# Smarty-BOTTOM.net
KiCad netlist of a schematic drawn in EAGLE
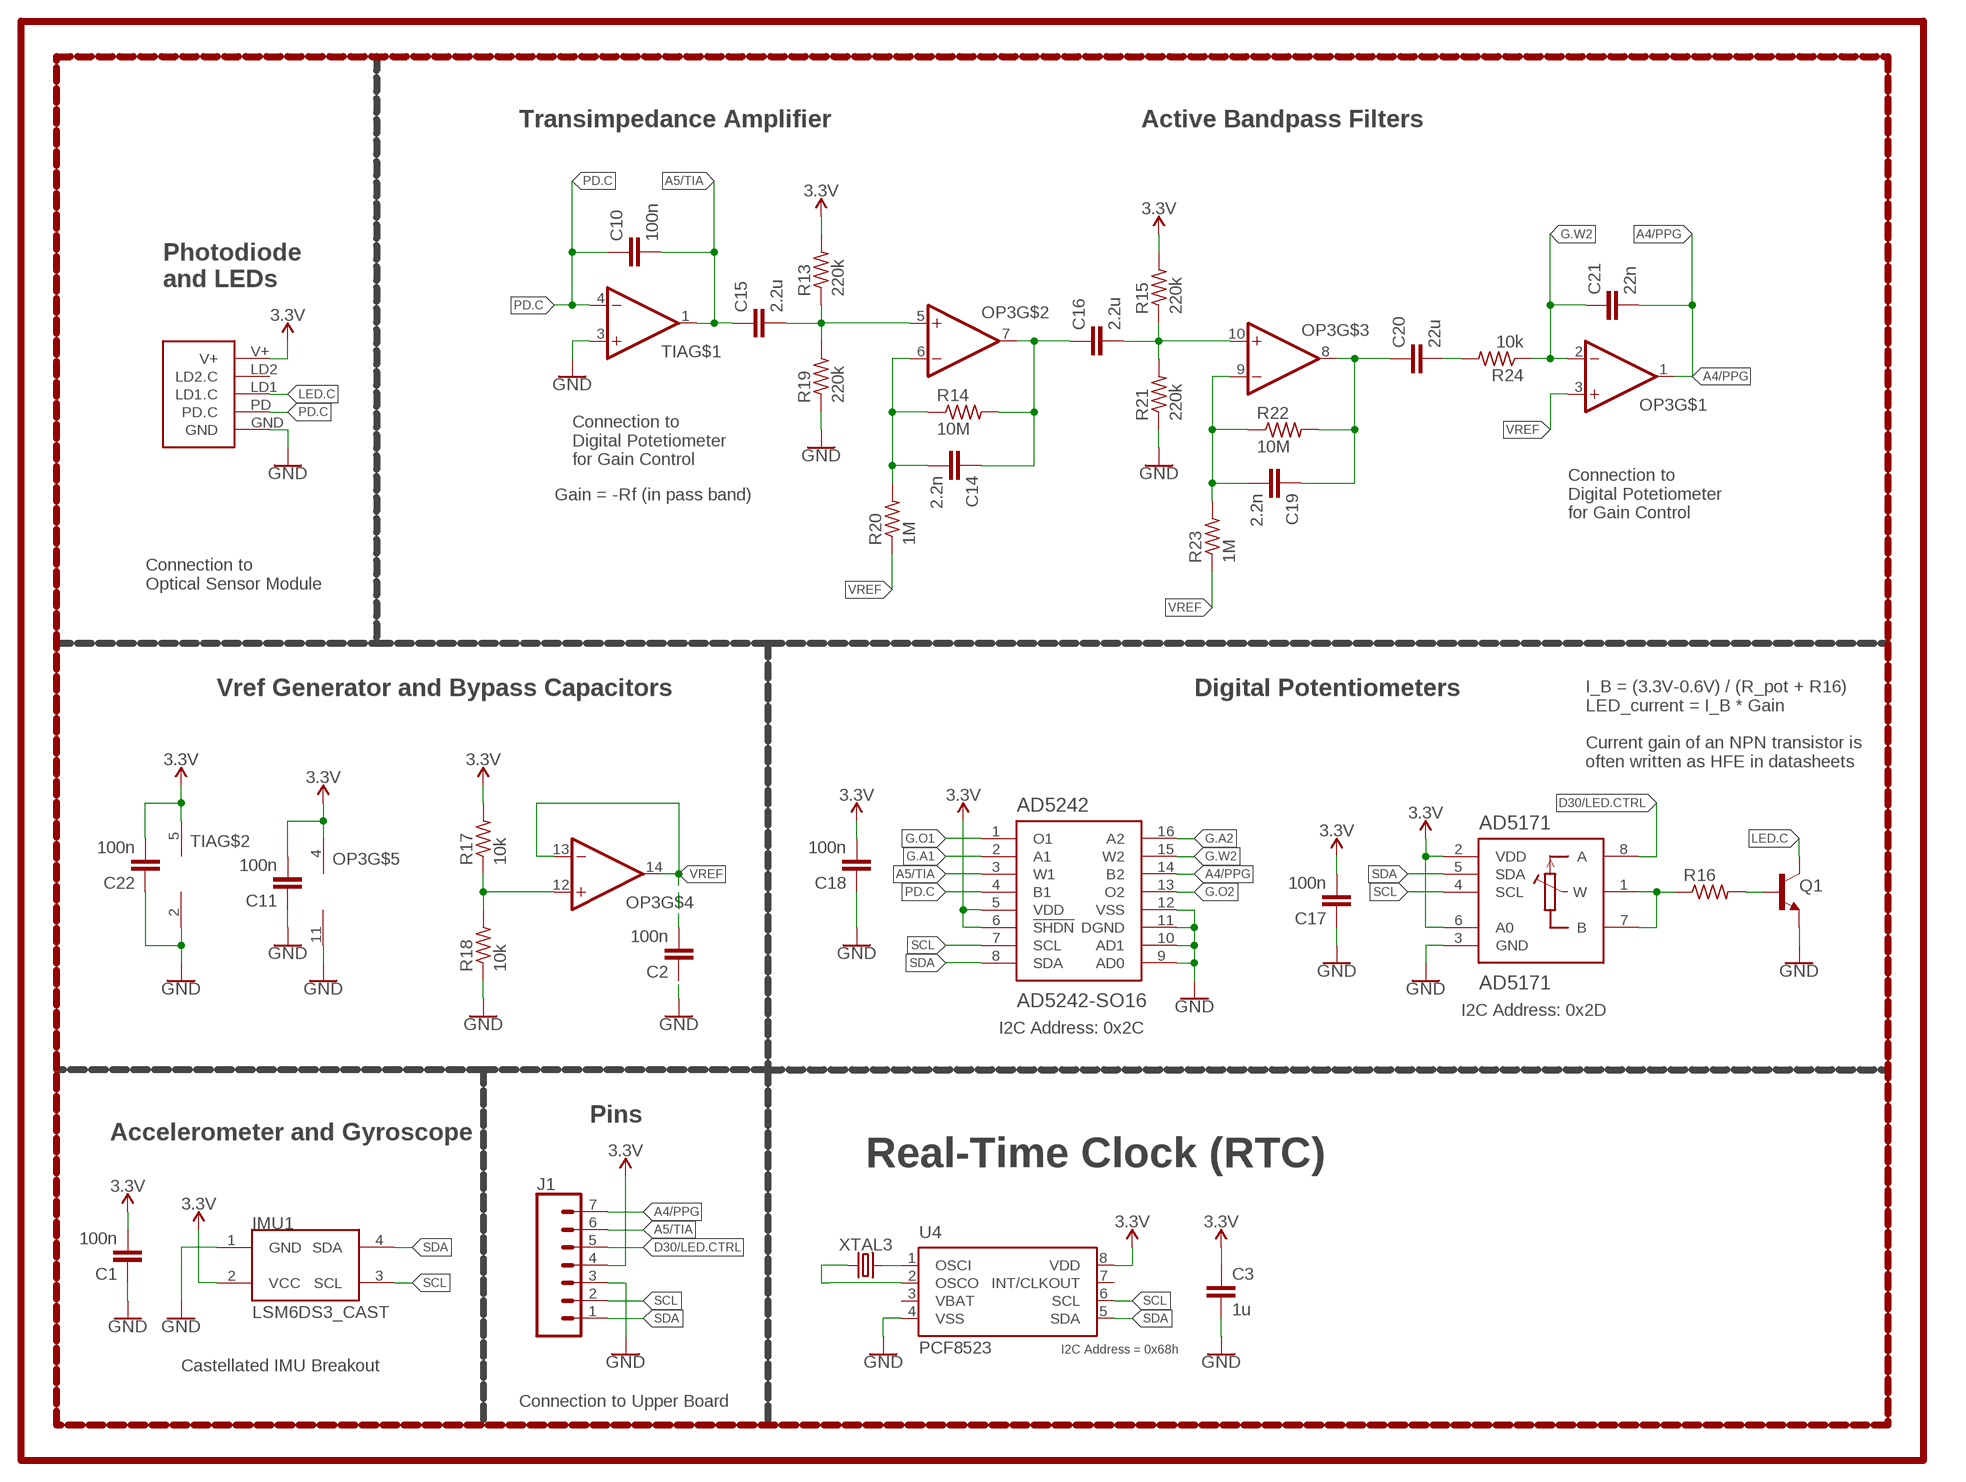
[diagram p0: schematic, sheet 1]

(export (version "E")
  (design (tool "Eeschema 10.0.6"))
  (components
    (comp (ref "AD5171")
      (value "AD5171")
      (footprint "eagle-import:SOT-23-8")
      (libsource (lib "eagle-import") (part "AD5171"))
    )
    (comp (ref "AD5242")
      (value "AD5242-SO16")
      (footprint "eagle-import:SO16")
      (libsource (lib "eagle-import") (part "AD5242-SO16"))
    )
    (comp (ref "C1")
      (value "100n")
      (footprint "eagle-import:C0603")
      (libsource (lib "eagle-import") (part "CAPACITOR0603"))
    )
    (comp (ref "C2")
      (value "100n")
      (footprint "eagle-import:C0603")
      (libsource (lib "eagle-import") (part "CAPACITOR0603"))
    )
    (comp (ref "C3")
      (value "1u")
      (footprint "eagle-import:C0603")
      (libsource (lib "eagle-import") (part "CAPACITOR0603"))
    )
    (comp (ref "C10")
      (value "100n")
      (footprint "eagle-import:C0603")
      (libsource (lib "eagle-import") (part "CAPACITOR0603"))
    )
    (comp (ref "C11")
      (value "100n")
      (footprint "eagle-import:C0603")
      (libsource (lib "eagle-import") (part "CAPACITOR0603"))
    )
    (comp (ref "C14")
      (value "2.2n")
      (footprint "eagle-import:C0603")
      (libsource (lib "eagle-import") (part "CAPACITOR0603"))
    )
    (comp (ref "C15")
      (value "2.2u")
      (footprint "eagle-import:C0603")
      (libsource (lib "eagle-import") (part "CAPACITOR0603"))
    )
    (comp (ref "C16")
      (value "2.2u")
      (footprint "eagle-import:C0603")
      (libsource (lib "eagle-import") (part "CAPACITOR0603"))
    )
    (comp (ref "C17")
      (value "100n")
      (footprint "eagle-import:C0603")
      (libsource (lib "eagle-import") (part "CAPACITOR0603"))
    )
    (comp (ref "C18")
      (value "100n")
      (footprint "eagle-import:C0603")
      (libsource (lib "eagle-import") (part "CAPACITOR0603"))
    )
    (comp (ref "C19")
      (value "2.2n")
      (footprint "eagle-import:C0603")
      (libsource (lib "eagle-import") (part "CAPACITOR0603"))
    )
    (comp (ref "C20")
      (value "22u")
      (footprint "eagle-import:C0603")
      (libsource (lib "eagle-import") (part "CAPACITOR0603"))
    )
    (comp (ref "C21")
      (value "22n")
      (footprint "eagle-import:C0603")
      (libsource (lib "eagle-import") (part "CAPACITOR0603"))
    )
    (comp (ref "C22")
      (value "100n")
      (footprint "eagle-import:C0603")
      (libsource (lib "eagle-import") (part "CAPACITOR0603"))
    )
    (comp (ref "IMU1")
      (value "LSM6DS3_CAST")
      (footprint "eagle-import:LSM6DS3_CAST")
      (libsource (lib "eagle-import") (part "LSM6DS3_CAST"))
    )
    (comp (ref "J1")
      (value "CONN_07-1.27MM")
      (footprint "eagle-import:1X07_1.27MM")
      (libsource (lib "eagle-import") (part "CONN_07-1.27MM"))
    )
    (comp (ref "OP3")
      (value "OP-QUAD-SO14")
      (footprint "eagle-import:SO14")
      (libsource (lib "eagle-import") (part "OP-QUAD-SO14"))
    )
    (comp (ref "Q1")
      (value "NPN-GENERIC")
      (footprint "eagle-import:SOT23-3")
      (libsource (lib "eagle-import") (part "NPN-GENERIC"))
    )
    (comp (ref "R13")
      (value "220k")
      (footprint "eagle-import:R0603")
      (libsource (lib "eagle-import") (part "RESISTOR0603"))
    )
    (comp (ref "R14")
      (value "10M")
      (footprint "eagle-import:R0603")
      (libsource (lib "eagle-import") (part "RESISTOR0603"))
    )
    (comp (ref "R15")
      (value "220k")
      (footprint "eagle-import:R0603")
      (libsource (lib "eagle-import") (part "RESISTOR0603"))
    )
    (comp (ref "R16")
      (value "RESISTOR0603")
      (footprint "eagle-import:R0603")
      (libsource (lib "eagle-import") (part "RESISTOR0603"))
    )
    (comp (ref "R17")
      (value "10k")
      (footprint "eagle-import:R0402")
      (libsource (lib "eagle-import") (part "RESISTOR0402"))
    )
    (comp (ref "R18")
      (value "10k")
      (footprint "eagle-import:R0402")
      (libsource (lib "eagle-import") (part "RESISTOR0402"))
    )
    (comp (ref "R19")
      (value "220k")
      (footprint "eagle-import:R0603")
      (libsource (lib "eagle-import") (part "RESISTOR0603"))
    )
    (comp (ref "R20")
      (value "1M")
      (footprint "eagle-import:R0603")
      (libsource (lib "eagle-import") (part "RESISTOR0603"))
    )
    (comp (ref "R21")
      (value "220k")
      (footprint "eagle-import:R0603")
      (libsource (lib "eagle-import") (part "RESISTOR0603"))
    )
    (comp (ref "R22")
      (value "10M")
      (footprint "eagle-import:R0603")
      (libsource (lib "eagle-import") (part "RESISTOR0603"))
    )
    (comp (ref "R23")
      (value "1M")
      (footprint "eagle-import:R0603")
      (libsource (lib "eagle-import") (part "RESISTOR0603"))
    )
    (comp (ref "R24")
      (value "10k")
      (footprint "eagle-import:R0603")
      (libsource (lib "eagle-import") (part "RESISTOR0603"))
    )
    (comp (ref "TIA")
      (value "OP-SINGLEOT")
      (footprint "eagle-import:SOT23-5")
      (libsource (lib "eagle-import") (part "OP-SINGLEOT"))
    )
    (comp (ref "U$3")
      (value "PPG.MODULE.2")
      (footprint "eagle-import:PPG.MODULE.2")
      (libsource (lib "eagle-import") (part "PPG.MODULE.2"))
    )
    (comp (ref "U4")
      (value "PCF8523")
      (footprint "eagle-import:SO8")
      (libsource (lib "eagle-import") (part "PCF8523"))
    )
    (comp (ref "XTAL3")
      (value "32.7680kHz")
      (footprint "eagle-import:2-SMD.NOLEAD.2.0MMTO1.2MM")
      (libsource (lib "eagle-import") (part "CRYSTALECS-.327-12.5-12-C-TR"))
    )
  )
  (nets
    (net (code "1") (name "/VBAT") (class "Default")
      (node (ref "U4") (pin "3") (pinfunction "VBAT_3") (pintype "power_in"))
    )
    (net (code "2") (name "3.3V") (class "Default")
      (node (ref "AD5171") (pin "2") (pinfunction "VDD_2") (pintype "bidirectional"))
      (node (ref "AD5171") (pin "6") (pinfunction "A0_6") (pintype "bidirectional"))
      (node (ref "AD5242") (pin "5") (pinfunction "VDD_5") (pintype "bidirectional"))
      (node (ref "AD5242") (pin "6") (pinfunction "~{SHDN}_6") (pintype "bidirectional"))
      (node (ref "C1") (pin "2") (pinfunction "2_2") (pintype "passive"))
      (node (ref "C11") (pin "2") (pinfunction "2_2") (pintype "passive"))
      (node (ref "C17") (pin "2") (pinfunction "2_2") (pintype "passive"))
      (node (ref "C18") (pin "2") (pinfunction "2_2") (pintype "passive"))
      (node (ref "C22") (pin "2") (pinfunction "2_2") (pintype "passive"))
      (node (ref "C3") (pin "1") (pinfunction "1_1") (pintype "passive"))
      (node (ref "IMU1") (pin "2") (pinfunction "VCC_2") (pintype "bidirectional"))
      (node (ref "J1") (pin "4") (pinfunction "4_4") (pintype "passive"))
      (node (ref "OP3") (pin "4") (pinfunction "V+_4") (pintype "power_in"))
      (node (ref "R13") (pin "2") (pinfunction "2_2") (pintype "passive"))
      (node (ref "R15") (pin "2") (pinfunction "2_2") (pintype "passive"))
      (node (ref "R17") (pin "2") (pinfunction "2_2") (pintype "passive"))
      (node (ref "TIA") (pin "5") (pinfunction "V+_5") (pintype "power_in"))
      (node (ref "U$3") (pin "V+") (pinfunction "V+_V+") (pintype "bidirectional"))
      (node (ref "U4") (pin "8") (pinfunction "VDD_8") (pintype "power_in"))
    )
    (net (code "3") (name "A4{slash}PPG") (class "Default")
      (node (ref "AD5242") (pin "14") (pinfunction "B2_14") (pintype "bidirectional"))
      (node (ref "C21") (pin "2") (pinfunction "2_2") (pintype "passive"))
      (node (ref "J1") (pin "7") (pinfunction "7_7") (pintype "passive"))
      (node (ref "OP3") (pin "1") (pinfunction "OUT_1") (pintype "output"))
    )
    (net (code "4") (name "A5{slash}TIA") (class "Default")
      (node (ref "AD5242") (pin "3") (pinfunction "W1_3") (pintype "bidirectional"))
      (node (ref "C10") (pin "2") (pinfunction "2_2") (pintype "passive"))
      (node (ref "C15") (pin "1") (pinfunction "1_1") (pintype "passive"))
      (node (ref "J1") (pin "6") (pinfunction "6_6") (pintype "passive"))
      (node (ref "TIA") (pin "1") (pinfunction "OUT_1") (pintype "output"))
    )
    (net (code "5") (name "D30{slash}LED.CTRL") (class "Default")
      (node (ref "AD5171") (pin "8") (pinfunction "A_8") (pintype "bidirectional"))
      (node (ref "J1") (pin "5") (pinfunction "5_5") (pintype "passive"))
    )
    (net (code "6") (name "G.A1") (class "Default")
      (node (ref "AD5242") (pin "2") (pinfunction "A1_2") (pintype "bidirectional"))
    )
    (net (code "7") (name "G.A2") (class "Default")
      (node (ref "AD5242") (pin "16") (pinfunction "A2_16") (pintype "bidirectional"))
    )
    (net (code "8") (name "G.O1") (class "Default")
      (node (ref "AD5242") (pin "1") (pinfunction "O1_1") (pintype "bidirectional"))
    )
    (net (code "9") (name "G.O2") (class "Default")
      (node (ref "AD5242") (pin "13") (pinfunction "O2_13") (pintype "bidirectional"))
    )
    (net (code "10") (name "G.W2") (class "Default")
      (node (ref "AD5242") (pin "15") (pinfunction "W2_15") (pintype "bidirectional"))
      (node (ref "C21") (pin "1") (pinfunction "1_1") (pintype "passive"))
      (node (ref "OP3") (pin "2") (pinfunction "-IN_2") (pintype "input"))
      (node (ref "R24") (pin "1") (pinfunction "1_1") (pintype "passive"))
    )
    (net (code "11") (name "GND") (class "Default")
      (node (ref "AD5171") (pin "3") (pinfunction "GND_3") (pintype "bidirectional"))
      (node (ref "AD5242") (pin "10") (pinfunction "AD1_10") (pintype "bidirectional"))
      (node (ref "AD5242") (pin "11") (pinfunction "DGND_11") (pintype "bidirectional"))
      (node (ref "AD5242") (pin "12") (pinfunction "VSS_12") (pintype "bidirectional"))
      (node (ref "AD5242") (pin "9") (pinfunction "AD0_9") (pintype "bidirectional"))
      (node (ref "C1") (pin "1") (pinfunction "1_1") (pintype "passive"))
      (node (ref "C11") (pin "1") (pinfunction "1_1") (pintype "passive"))
      (node (ref "C17") (pin "1") (pinfunction "1_1") (pintype "passive"))
      (node (ref "C18") (pin "1") (pinfunction "1_1") (pintype "passive"))
      (node (ref "C2") (pin "1") (pinfunction "1_1") (pintype "passive"))
      (node (ref "C22") (pin "1") (pinfunction "1_1") (pintype "passive"))
      (node (ref "C3") (pin "2") (pinfunction "2_2") (pintype "passive"))
      (node (ref "IMU1") (pin "1") (pinfunction "GND_1") (pintype "bidirectional"))
      (node (ref "J1") (pin "3") (pinfunction "3_3") (pintype "passive"))
      (node (ref "OP3") (pin "11") (pinfunction "V-_11") (pintype "power_in"))
      (node (ref "Q1") (pin "2") (pinfunction "E_2") (pintype "passive"))
      (node (ref "R18") (pin "1") (pinfunction "1_1") (pintype "passive"))
      (node (ref "R19") (pin "1") (pinfunction "1_1") (pintype "passive"))
      (node (ref "R21") (pin "1") (pinfunction "1_1") (pintype "passive"))
      (node (ref "TIA") (pin "2") (pinfunction "V-_2") (pintype "power_in"))
      (node (ref "TIA") (pin "3") (pinfunction "+IN_3") (pintype "input"))
      (node (ref "U$3") (pin "GND") (pinfunction "GND_GND") (pintype "bidirectional"))
      (node (ref "U4") (pin "4") (pinfunction "VSS_4") (pintype "power_in"))
    )
    (net (code "12") (name "LED.C") (class "Default")
      (node (ref "Q1") (pin "3") (pinfunction "C_3") (pintype "passive"))
      (node (ref "U$3") (pin "LD1") (pinfunction "LD1.C_LD1") (pintype "bidirectional"))
    )
    (net (code "13") (name "Net-(AD5171-B)") (class "Default")
      (node (ref "AD5171") (pin "1") (pinfunction "W_1") (pintype "bidirectional"))
      (node (ref "AD5171") (pin "7") (pinfunction "B_7") (pintype "bidirectional"))
      (node (ref "R16") (pin "1") (pinfunction "1_1") (pintype "passive"))
    )
    (net (code "14") (name "Net-(C20-Pad2)") (class "Default")
      (node (ref "C20") (pin "2") (pinfunction "2_2") (pintype "passive"))
      (node (ref "R24") (pin "2") (pinfunction "2_2") (pintype "passive"))
    )
    (net (code "15") (name "Net-(OP3B-+IN)") (class "Default")
      (node (ref "C15") (pin "2") (pinfunction "2_2") (pintype "passive"))
      (node (ref "OP3") (pin "5") (pinfunction "+IN_5") (pintype "input"))
      (node (ref "R13") (pin "1") (pinfunction "1_1") (pintype "passive"))
      (node (ref "R19") (pin "2") (pinfunction "2_2") (pintype "passive"))
    )
    (net (code "16") (name "Net-(OP3B--IN)") (class "Default")
      (node (ref "C14") (pin "2") (pinfunction "2_2") (pintype "passive"))
      (node (ref "OP3") (pin "6") (pinfunction "-IN_6") (pintype "input"))
      (node (ref "R14") (pin "1") (pinfunction "1_1") (pintype "passive"))
      (node (ref "R20") (pin "2") (pinfunction "2_2") (pintype "passive"))
    )
    (net (code "17") (name "Net-(OP3B-OUT)") (class "Default")
      (node (ref "C14") (pin "1") (pinfunction "1_1") (pintype "passive"))
      (node (ref "C16") (pin "1") (pinfunction "1_1") (pintype "passive"))
      (node (ref "OP3") (pin "7") (pinfunction "OUT_7") (pintype "output"))
      (node (ref "R14") (pin "2") (pinfunction "2_2") (pintype "passive"))
    )
    (net (code "18") (name "Net-(OP3C-+IN)") (class "Default")
      (node (ref "C16") (pin "2") (pinfunction "2_2") (pintype "passive"))
      (node (ref "OP3") (pin "10") (pinfunction "+IN_10") (pintype "input"))
      (node (ref "R15") (pin "1") (pinfunction "1_1") (pintype "passive"))
      (node (ref "R21") (pin "2") (pinfunction "2_2") (pintype "passive"))
    )
    (net (code "19") (name "Net-(OP3C--IN)") (class "Default")
      (node (ref "C19") (pin "2") (pinfunction "2_2") (pintype "passive"))
      (node (ref "OP3") (pin "9") (pinfunction "-IN_9") (pintype "input"))
      (node (ref "R22") (pin "1") (pinfunction "1_1") (pintype "passive"))
      (node (ref "R23") (pin "2") (pinfunction "2_2") (pintype "passive"))
    )
    (net (code "20") (name "Net-(OP3C-OUT)") (class "Default")
      (node (ref "C19") (pin "1") (pinfunction "1_1") (pintype "passive"))
      (node (ref "C20") (pin "1") (pinfunction "1_1") (pintype "passive"))
      (node (ref "OP3") (pin "8") (pinfunction "OUT_8") (pintype "output"))
      (node (ref "R22") (pin "2") (pinfunction "2_2") (pintype "passive"))
    )
    (net (code "21") (name "Net-(OP3D-+IN)") (class "Default")
      (node (ref "OP3") (pin "12") (pinfunction "+IN_12") (pintype "input"))
      (node (ref "R17") (pin "1") (pinfunction "1_1") (pintype "passive"))
      (node (ref "R18") (pin "2") (pinfunction "2_2") (pintype "passive"))
    )
    (net (code "22") (name "Net-(Q1-B)") (class "Default")
      (node (ref "Q1") (pin "1") (pinfunction "B_1") (pintype "passive"))
      (node (ref "R16") (pin "2") (pinfunction "2_2") (pintype "passive"))
    )
    (net (code "23") (name "Net-(U4-OSCI)") (class "Default")
      (node (ref "U4") (pin "1") (pinfunction "OSCI_1") (pintype "bidirectional"))
      (node (ref "XTAL3") (pin "P$2") (pinfunction "2_P$2") (pintype "passive"))
    )
    (net (code "24") (name "Net-(U4-OSCO)") (class "Default")
      (node (ref "U4") (pin "2") (pinfunction "OSCO_2") (pintype "bidirectional"))
      (node (ref "XTAL3") (pin "P$1") (pinfunction "1_P$1") (pintype "passive"))
    )
    (net (code "25") (name "PD.C") (class "Default")
      (node (ref "AD5242") (pin "4") (pinfunction "B1_4") (pintype "bidirectional"))
      (node (ref "C10") (pin "1") (pinfunction "1_1") (pintype "passive"))
      (node (ref "TIA") (pin "4") (pinfunction "-IN_4") (pintype "input"))
      (node (ref "U$3") (pin "PD") (pinfunction "PD.C_PD") (pintype "bidirectional"))
    )
    (net (code "26") (name "SCL") (class "Default")
      (node (ref "AD5171") (pin "4") (pinfunction "SCL_4") (pintype "bidirectional"))
      (node (ref "AD5242") (pin "7") (pinfunction "SCL_7") (pintype "bidirectional"))
      (node (ref "IMU1") (pin "3") (pinfunction "SCL_3") (pintype "bidirectional"))
      (node (ref "J1") (pin "2") (pinfunction "2_2") (pintype "passive"))
      (node (ref "U4") (pin "6") (pinfunction "SCL_6") (pintype "bidirectional"))
    )
    (net (code "27") (name "SDA") (class "Default")
      (node (ref "AD5171") (pin "5") (pinfunction "SDA_5") (pintype "bidirectional"))
      (node (ref "AD5242") (pin "8") (pinfunction "SDA_8") (pintype "bidirectional"))
      (node (ref "IMU1") (pin "4") (pinfunction "SDA_4") (pintype "bidirectional"))
      (node (ref "J1") (pin "1") (pinfunction "1_1") (pintype "passive"))
      (node (ref "U4") (pin "5") (pinfunction "SDA_5") (pintype "bidirectional"))
    )
    (net (code "28") (name "VREF") (class "Default")
      (node (ref "C2") (pin "2") (pinfunction "2_2") (pintype "passive"))
      (node (ref "OP3") (pin "13") (pinfunction "-IN_13") (pintype "input"))
      (node (ref "OP3") (pin "14") (pinfunction "OUT_14") (pintype "output"))
      (node (ref "OP3") (pin "3") (pinfunction "+IN_3") (pintype "input"))
      (node (ref "R20") (pin "1") (pinfunction "1_1") (pintype "passive"))
      (node (ref "R23") (pin "1") (pinfunction "1_1") (pintype "passive"))
    )
    (net (code "29") (name "unconnected-(U$3-LD2.C-PadLD2)") (class "Default")
      (node (ref "U$3") (pin "LD2") (pinfunction "LD2.C_LD2") (pintype "bidirectional"))
    )
    (net (code "30") (name "unconnected-(U4-INT{slash}CLKOUT-Pad7)") (class "Default")
      (node (ref "U4") (pin "7") (pinfunction "INT/CLKOUT_7") (pintype "bidirectional"))
    )
  )
)
